# LED_Board_-_SCH_v1_0_0_20210410.net
KiCad netlist of a schematic drawn in Altium Designer
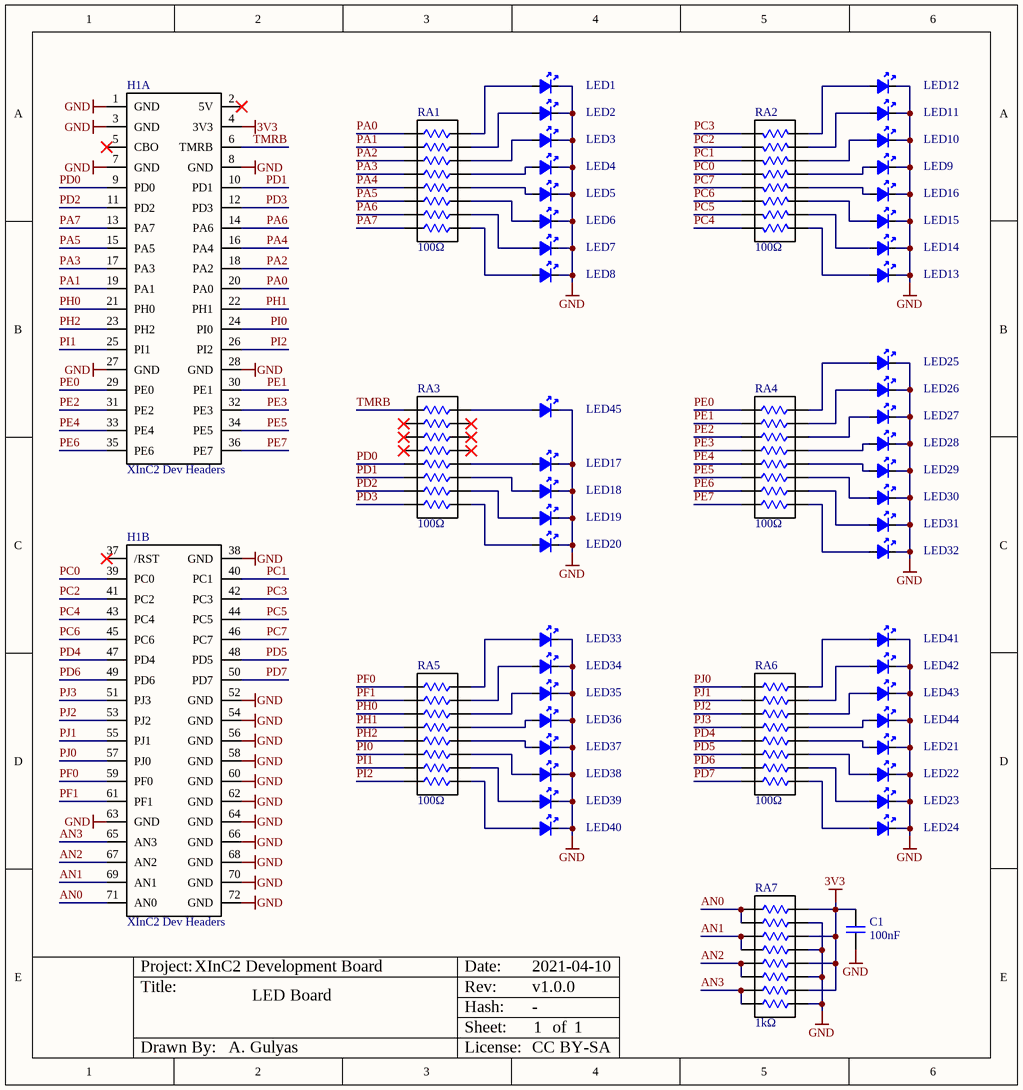
[diagram p0: LED Board - SCH v1.0.0 20210410.SchDoc]

(export (version "E")
  (design (tool "Eeschema 10.0.6"))
  (components
    (comp (ref "C1")
      (value "100nF")
      (footprint "0603 - C")
      (description "CAP CER 0.1UF 16V X7R 0603")
      (fields (field (name "MFG") "Yageo") (field (name "TOLERANCE") "±10%"))
      (libsource (lib "Public Library") (part "C - 0603 - 100nF - 16V"))
    )
    (comp (ref "H1")
      (value "XInC2 Dev Headers")
      (footprint "XInC2 Dev Shield")
      (description "Two 2x16 female headers than mate with a XInC2 Dev Board")
      (libsource (lib "Public Library") (part "XInC2 Dev 2 Shield"))
    )
    (comp (ref "LED1")
      (value "Red")
      (footprint "LED - RED - TH")
      (description "LED RED DIFFUSED 5MM ROUND T/H")
      (fields (field (name "MFG") "Würth Elektronik"))
      (libsource (lib "Public Library") (part "LED - TH - Red"))
    )
    (comp (ref "LED2")
      (value "Red")
      (footprint "LED - RED - TH")
      (description "LED RED DIFFUSED 5MM ROUND T/H")
      (fields (field (name "MFG") "Würth Elektronik"))
      (libsource (lib "Public Library") (part "LED - TH - Red"))
    )
    (comp (ref "LED3")
      (value "Red")
      (footprint "LED - RED - TH")
      (description "LED RED DIFFUSED 5MM ROUND T/H")
      (fields (field (name "MFG") "Würth Elektronik"))
      (libsource (lib "Public Library") (part "LED - TH - Red"))
    )
    (comp (ref "LED4")
      (value "Red")
      (footprint "LED - RED - TH")
      (description "LED RED DIFFUSED 5MM ROUND T/H")
      (fields (field (name "MFG") "Würth Elektronik"))
      (libsource (lib "Public Library") (part "LED - TH - Red"))
    )
    (comp (ref "LED5")
      (value "Red")
      (footprint "LED - RED - TH")
      (description "LED RED DIFFUSED 5MM ROUND T/H")
      (fields (field (name "MFG") "Würth Elektronik"))
      (libsource (lib "Public Library") (part "LED - TH - Red"))
    )
    (comp (ref "LED6")
      (value "Red")
      (footprint "LED - RED - TH")
      (description "LED RED DIFFUSED 5MM ROUND T/H")
      (fields (field (name "MFG") "Würth Elektronik"))
      (libsource (lib "Public Library") (part "LED - TH - Red"))
    )
    (comp (ref "LED7")
      (value "Red")
      (footprint "LED - RED - TH")
      (description "LED RED DIFFUSED 5MM ROUND T/H")
      (fields (field (name "MFG") "Würth Elektronik"))
      (libsource (lib "Public Library") (part "LED - TH - Red"))
    )
    (comp (ref "LED8")
      (value "Red")
      (footprint "LED - RED - TH")
      (description "LED RED DIFFUSED 5MM ROUND T/H")
      (fields (field (name "MFG") "Würth Elektronik"))
      (libsource (lib "Public Library") (part "LED - TH - Red"))
    )
    (comp (ref "LED9")
      (value "Red")
      (footprint "LED - RED - TH")
      (description "LED RED DIFFUSED 5MM ROUND T/H")
      (fields (field (name "MFG") "Würth Elektronik"))
      (libsource (lib "Public Library") (part "LED - TH - Red"))
    )
    (comp (ref "LED10")
      (value "Red")
      (footprint "LED - RED - TH")
      (description "LED RED DIFFUSED 5MM ROUND T/H")
      (fields (field (name "MFG") "Würth Elektronik"))
      (libsource (lib "Public Library") (part "LED - TH - Red"))
    )
    (comp (ref "LED11")
      (value "Red")
      (footprint "LED - RED - TH")
      (description "LED RED DIFFUSED 5MM ROUND T/H")
      (fields (field (name "MFG") "Würth Elektronik"))
      (libsource (lib "Public Library") (part "LED - TH - Red"))
    )
    (comp (ref "LED12")
      (value "Red")
      (footprint "LED - RED - TH")
      (description "LED RED DIFFUSED 5MM ROUND T/H")
      (fields (field (name "MFG") "Würth Elektronik"))
      (libsource (lib "Public Library") (part "LED - TH - Red"))
    )
    (comp (ref "LED13")
      (value "Red")
      (footprint "LED - RED - TH")
      (description "LED RED DIFFUSED 5MM ROUND T/H")
      (fields (field (name "MFG") "Würth Elektronik"))
      (libsource (lib "Public Library") (part "LED - TH - Red"))
    )
    (comp (ref "LED14")
      (value "Red")
      (footprint "LED - RED - TH")
      (description "LED RED DIFFUSED 5MM ROUND T/H")
      (fields (field (name "MFG") "Würth Elektronik"))
      (libsource (lib "Public Library") (part "LED - TH - Red"))
    )
    (comp (ref "LED15")
      (value "Red")
      (footprint "LED - RED - TH")
      (description "LED RED DIFFUSED 5MM ROUND T/H")
      (fields (field (name "MFG") "Würth Elektronik"))
      (libsource (lib "Public Library") (part "LED - TH - Red"))
    )
    (comp (ref "LED16")
      (value "Red")
      (footprint "LED - RED - TH")
      (description "LED RED DIFFUSED 5MM ROUND T/H")
      (fields (field (name "MFG") "Würth Elektronik"))
      (libsource (lib "Public Library") (part "LED - TH - Red"))
    )
    (comp (ref "LED17")
      (value "Red")
      (footprint "LED - RED - TH")
      (description "LED RED DIFFUSED 5MM ROUND T/H")
      (fields (field (name "MFG") "Würth Elektronik"))
      (libsource (lib "Public Library") (part "LED - TH - Red"))
    )
    (comp (ref "LED18")
      (value "Red")
      (footprint "LED - RED - TH")
      (description "LED RED DIFFUSED 5MM ROUND T/H")
      (fields (field (name "MFG") "Würth Elektronik"))
      (libsource (lib "Public Library") (part "LED - TH - Red"))
    )
    (comp (ref "LED19")
      (value "Red")
      (footprint "LED - RED - TH")
      (description "LED RED DIFFUSED 5MM ROUND T/H")
      (fields (field (name "MFG") "Würth Elektronik"))
      (libsource (lib "Public Library") (part "LED - TH - Red"))
    )
    (comp (ref "LED20")
      (value "Red")
      (footprint "LED - RED - TH")
      (description "LED RED DIFFUSED 5MM ROUND T/H")
      (fields (field (name "MFG") "Würth Elektronik"))
      (libsource (lib "Public Library") (part "LED - TH - Red"))
    )
    (comp (ref "LED21")
      (value "Red")
      (footprint "LED - RED - TH")
      (description "LED RED DIFFUSED 5MM ROUND T/H")
      (fields (field (name "MFG") "Würth Elektronik"))
      (libsource (lib "Public Library") (part "LED - TH - Red"))
    )
    (comp (ref "LED22")
      (value "Red")
      (footprint "LED - RED - TH")
      (description "LED RED DIFFUSED 5MM ROUND T/H")
      (fields (field (name "MFG") "Würth Elektronik"))
      (libsource (lib "Public Library") (part "LED - TH - Red"))
    )
    (comp (ref "LED23")
      (value "Red")
      (footprint "LED - RED - TH")
      (description "LED RED DIFFUSED 5MM ROUND T/H")
      (fields (field (name "MFG") "Würth Elektronik"))
      (libsource (lib "Public Library") (part "LED - TH - Red"))
    )
    (comp (ref "LED24")
      (value "Red")
      (footprint "LED - RED - TH")
      (description "LED RED DIFFUSED 5MM ROUND T/H")
      (fields (field (name "MFG") "Würth Elektronik"))
      (libsource (lib "Public Library") (part "LED - TH - Red"))
    )
    (comp (ref "LED25")
      (value "Red")
      (footprint "LED - RED - TH")
      (description "LED RED DIFFUSED 5MM ROUND T/H")
      (fields (field (name "MFG") "Würth Elektronik"))
      (libsource (lib "Public Library") (part "LED - TH - Red"))
    )
    (comp (ref "LED26")
      (value "Red")
      (footprint "LED - RED - TH")
      (description "LED RED DIFFUSED 5MM ROUND T/H")
      (fields (field (name "MFG") "Würth Elektronik"))
      (libsource (lib "Public Library") (part "LED - TH - Red"))
    )
    (comp (ref "LED27")
      (value "Red")
      (footprint "LED - RED - TH")
      (description "LED RED DIFFUSED 5MM ROUND T/H")
      (fields (field (name "MFG") "Würth Elektronik"))
      (libsource (lib "Public Library") (part "LED - TH - Red"))
    )
    (comp (ref "LED28")
      (value "Red")
      (footprint "LED - RED - TH")
      (description "LED RED DIFFUSED 5MM ROUND T/H")
      (fields (field (name "MFG") "Würth Elektronik"))
      (libsource (lib "Public Library") (part "LED - TH - Red"))
    )
    (comp (ref "LED29")
      (value "Red")
      (footprint "LED - RED - TH")
      (description "LED RED DIFFUSED 5MM ROUND T/H")
      (fields (field (name "MFG") "Würth Elektronik"))
      (libsource (lib "Public Library") (part "LED - TH - Red"))
    )
    (comp (ref "LED30")
      (value "Red")
      (footprint "LED - RED - TH")
      (description "LED RED DIFFUSED 5MM ROUND T/H")
      (fields (field (name "MFG") "Würth Elektronik"))
      (libsource (lib "Public Library") (part "LED - TH - Red"))
    )
    (comp (ref "LED31")
      (value "Red")
      (footprint "LED - RED - TH")
      (description "LED RED DIFFUSED 5MM ROUND T/H")
      (fields (field (name "MFG") "Würth Elektronik"))
      (libsource (lib "Public Library") (part "LED - TH - Red"))
    )
    (comp (ref "LED32")
      (value "Red")
      (footprint "LED - RED - TH")
      (description "LED RED DIFFUSED 5MM ROUND T/H")
      (fields (field (name "MFG") "Würth Elektronik"))
      (libsource (lib "Public Library") (part "LED - TH - Red"))
    )
    (comp (ref "LED33")
      (value "Red")
      (footprint "LED - RED - TH")
      (description "LED RED DIFFUSED 5MM ROUND T/H")
      (fields (field (name "MFG") "Würth Elektronik"))
      (libsource (lib "Public Library") (part "LED - TH - Red"))
    )
    (comp (ref "LED34")
      (value "Red")
      (footprint "LED - RED - TH")
      (description "LED RED DIFFUSED 5MM ROUND T/H")
      (fields (field (name "MFG") "Würth Elektronik"))
      (libsource (lib "Public Library") (part "LED - TH - Red"))
    )
    (comp (ref "LED35")
      (value "Red")
      (footprint "LED - RED - TH")
      (description "LED RED DIFFUSED 5MM ROUND T/H")
      (fields (field (name "MFG") "Würth Elektronik"))
      (libsource (lib "Public Library") (part "LED - TH - Red"))
    )
    (comp (ref "LED36")
      (value "Red")
      (footprint "LED - RED - TH")
      (description "LED RED DIFFUSED 5MM ROUND T/H")
      (fields (field (name "MFG") "Würth Elektronik"))
      (libsource (lib "Public Library") (part "LED - TH - Red"))
    )
    (comp (ref "LED37")
      (value "Red")
      (footprint "LED - RED - TH")
      (description "LED RED DIFFUSED 5MM ROUND T/H")
      (fields (field (name "MFG") "Würth Elektronik"))
      (libsource (lib "Public Library") (part "LED - TH - Red"))
    )
    (comp (ref "LED38")
      (value "Red")
      (footprint "LED - RED - TH")
      (description "LED RED DIFFUSED 5MM ROUND T/H")
      (fields (field (name "MFG") "Würth Elektronik"))
      (libsource (lib "Public Library") (part "LED - TH - Red"))
    )
    (comp (ref "LED39")
      (value "Red")
      (footprint "LED - RED - TH")
      (description "LED RED DIFFUSED 5MM ROUND T/H")
      (fields (field (name "MFG") "Würth Elektronik"))
      (libsource (lib "Public Library") (part "LED - TH - Red"))
    )
    (comp (ref "LED40")
      (value "Red")
      (footprint "LED - RED - TH")
      (description "LED RED DIFFUSED 5MM ROUND T/H")
      (fields (field (name "MFG") "Würth Elektronik"))
      (libsource (lib "Public Library") (part "LED - TH - Red"))
    )
    (comp (ref "LED41")
      (value "Red")
      (footprint "LED - RED - TH")
      (description "LED RED DIFFUSED 5MM ROUND T/H")
      (fields (field (name "MFG") "Würth Elektronik"))
      (libsource (lib "Public Library") (part "LED - TH - Red"))
    )
    (comp (ref "LED42")
      (value "Red")
      (footprint "LED - RED - TH")
      (description "LED RED DIFFUSED 5MM ROUND T/H")
      (fields (field (name "MFG") "Würth Elektronik"))
      (libsource (lib "Public Library") (part "LED - TH - Red"))
    )
    (comp (ref "LED43")
      (value "Red")
      (footprint "LED - RED - TH")
      (description "LED RED DIFFUSED 5MM ROUND T/H")
      (fields (field (name "MFG") "Würth Elektronik"))
      (libsource (lib "Public Library") (part "LED - TH - Red"))
    )
    (comp (ref "LED44")
      (value "Red")
      (footprint "LED - RED - TH")
      (description "LED RED DIFFUSED 5MM ROUND T/H")
      (fields (field (name "MFG") "Würth Elektronik"))
      (libsource (lib "Public Library") (part "LED - TH - Red"))
    )
    (comp (ref "LED45")
      (value "Red")
      (footprint "LED - RED - TH")
      (description "LED RED DIFFUSED 5MM ROUND T/H")
      (fields (field (name "MFG") "Würth Elektronik"))
      (libsource (lib "Public Library") (part "LED - TH - Red"))
    )
    (comp (ref "RA1")
      (value "100Ω")
      (footprint "0616 - 8 R array")
      (description "RES ARRAY 8 RES 100 OHM 1606")
      (fields (field (name "TOLERANCE") "±5%"))
      (libsource (lib "") (part "RA - 100Ω - 8_1"))
    )
    (comp (ref "RA2")
      (value "100Ω")
      (footprint "0616 - 8 R array")
      (description "RES ARRAY 8 RES 100 OHM 1606")
      (fields (field (name "TOLERANCE") "±5%"))
      (libsource (lib "Public Library") (part "RA - 100Ω - 8"))
    )
    (comp (ref "RA3")
      (value "100Ω")
      (footprint "0616 - 8 R array")
      (description "RES ARRAY 8 RES 100 OHM 1606")
      (fields (field (name "TOLERANCE") "±5%"))
      (libsource (lib "") (part "RA - 100Ω - 8_1"))
    )
    (comp (ref "RA4")
      (value "100Ω")
      (footprint "0616 - 8 R array")
      (description "RES ARRAY 8 RES 100 OHM 1606")
      (fields (field (name "TOLERANCE") "±5%"))
      (libsource (lib "") (part "RA - 100Ω - 8_1"))
    )
    (comp (ref "RA5")
      (value "100Ω")
      (footprint "0616 - 8 R array")
      (description "RES ARRAY 8 RES 100 OHM 1606")
      (fields (field (name "TOLERANCE") "±5%"))
      (libsource (lib "") (part "RA - 100Ω - 8_1"))
    )
    (comp (ref "RA6")
      (value "100Ω")
      (footprint "0616 - 8 R array")
      (description "RES ARRAY 8 RES 100 OHM 1606")
      (fields (field (name "TOLERANCE") "±5%"))
      (libsource (lib "") (part "RA - 100Ω - 8_2"))
    )
    (comp (ref "RA7")
      (value "1kΩ")
      (footprint "0616 - 8 R array")
      (description "RES ARRAY 8 RES 1K OHM 1606")
      (fields (field (name "TOLERANCE") "±5%"))
      (libsource (lib "Public Library") (part "RA - 1kΩ - 8"))
    )
  )
  (nets
    (net (code "1") (name "/AN0") (class "Default")
      (node (ref "H1") (pin "71") (pinfunction "AN0_71") (pintype "passive"))
      (node (ref "RA7") (pin "10") (pinfunction "10_10") (pintype "passive"))
      (node (ref "RA7") (pin "9") (pinfunction "9_9") (pintype "passive"))
    )
    (net (code "2") (name "/AN1") (class "Default")
      (node (ref "H1") (pin "69") (pinfunction "AN1_69") (pintype "passive"))
      (node (ref "RA7") (pin "11") (pinfunction "11_11") (pintype "passive"))
      (node (ref "RA7") (pin "12") (pinfunction "12_12") (pintype "passive"))
    )
    (net (code "3") (name "/AN2") (class "Default")
      (node (ref "H1") (pin "67") (pinfunction "AN2_67") (pintype "passive"))
      (node (ref "RA7") (pin "13") (pinfunction "13_13") (pintype "passive"))
      (node (ref "RA7") (pin "14") (pinfunction "14_14") (pintype "passive"))
    )
    (net (code "4") (name "/AN3") (class "Default")
      (node (ref "H1") (pin "65") (pinfunction "AN3_65") (pintype "passive"))
      (node (ref "RA7") (pin "15") (pinfunction "15_15") (pintype "passive"))
      (node (ref "RA7") (pin "16") (pinfunction "16_16") (pintype "passive"))
    )
    (net (code "5") (name "/PA0") (class "Default")
      (node (ref "H1") (pin "20") (pinfunction "PA0_20") (pintype "passive"))
      (node (ref "RA1") (pin "1") (pinfunction "1_1") (pintype "passive"))
    )
    (net (code "6") (name "/PA1") (class "Default")
      (node (ref "H1") (pin "19") (pinfunction "PA1_19") (pintype "passive"))
      (node (ref "RA1") (pin "2") (pinfunction "2_2") (pintype "passive"))
    )
    (net (code "7") (name "/PA2") (class "Default")
      (node (ref "H1") (pin "18") (pinfunction "PA2_18") (pintype "passive"))
      (node (ref "RA1") (pin "3") (pinfunction "3_3") (pintype "passive"))
    )
    (net (code "8") (name "/PA3") (class "Default")
      (node (ref "H1") (pin "17") (pinfunction "PA3_17") (pintype "passive"))
      (node (ref "RA1") (pin "4") (pinfunction "4_4") (pintype "passive"))
    )
    (net (code "9") (name "/PA4") (class "Default")
      (node (ref "H1") (pin "16") (pinfunction "PA4_16") (pintype "passive"))
      (node (ref "RA1") (pin "5") (pinfunction "5_5") (pintype "passive"))
    )
    (net (code "10") (name "/PA5") (class "Default")
      (node (ref "H1") (pin "15") (pinfunction "PA5_15") (pintype "passive"))
      (node (ref "RA1") (pin "6") (pinfunction "6_6") (pintype "passive"))
    )
    (net (code "11") (name "/PA6") (class "Default")
      (node (ref "H1") (pin "14") (pinfunction "PA6_14") (pintype "passive"))
      (node (ref "RA1") (pin "7") (pinfunction "7_7") (pintype "passive"))
    )
    (net (code "12") (name "/PA7") (class "Default")
      (node (ref "H1") (pin "13") (pinfunction "PA7_13") (pintype "passive"))
      (node (ref "RA1") (pin "8") (pinfunction "8_8") (pintype "passive"))
    )
    (net (code "13") (name "/PC0") (class "Default")
      (node (ref "H1") (pin "39") (pinfunction "PC0_39") (pintype "passive"))
      (node (ref "RA2") (pin "13") (pinfunction "13_13") (pintype "passive"))
    )
    (net (code "14") (name "/PC1") (class "Default")
      (node (ref "H1") (pin "40") (pinfunction "PC1_40") (pintype "passive"))
      (node (ref "RA2") (pin "14") (pinfunction "14_14") (pintype "passive"))
    )
    (net (code "15") (name "/PC2") (class "Default")
      (node (ref "H1") (pin "41") (pinfunction "PC2_41") (pintype "passive"))
      (node (ref "RA2") (pin "15") (pinfunction "15_15") (pintype "passive"))
    )
    (net (code "16") (name "/PC3") (class "Default")
      (node (ref "H1") (pin "42") (pinfunction "PC3_42") (pintype "passive"))
      (node (ref "RA2") (pin "16") (pinfunction "16_16") (pintype "passive"))
    )
    (net (code "17") (name "/PC4") (class "Default")
      (node (ref "H1") (pin "43") (pinfunction "PC4_43") (pintype "passive"))
      (node (ref "RA2") (pin "9") (pinfunction "9_9") (pintype "passive"))
    )
    (net (code "18") (name "/PC5") (class "Default")
      (node (ref "H1") (pin "44") (pinfunction "PC5_44") (pintype "passive"))
      (node (ref "RA2") (pin "10") (pinfunction "10_10") (pintype "passive"))
    )
    (net (code "19") (name "/PC6") (class "Default")
      (node (ref "H1") (pin "45") (pinfunction "PC6_45") (pintype "passive"))
      (node (ref "RA2") (pin "11") (pinfunction "11_11") (pintype "passive"))
    )
    (net (code "20") (name "/PC7") (class "Default")
      (node (ref "H1") (pin "46") (pinfunction "PC7_46") (pintype "passive"))
      (node (ref "RA2") (pin "12") (pinfunction "12_12") (pintype "passive"))
    )
    (net (code "21") (name "/PD0") (class "Default")
      (node (ref "H1") (pin "9") (pinfunction "PD0_9") (pintype "passive"))
      (node (ref "RA3") (pin "5") (pinfunction "5_5") (pintype "passive"))
    )
    (net (code "22") (name "/PD1") (class "Default")
      (node (ref "H1") (pin "10") (pinfunction "PD1_10") (pintype "passive"))
      (node (ref "RA3") (pin "6") (pinfunction "6_6") (pintype "passive"))
    )
    (net (code "23") (name "/PD2") (class "Default")
      (node (ref "H1") (pin "11") (pinfunction "PD2_11") (pintype "passive"))
      (node (ref "RA3") (pin "7") (pinfunction "7_7") (pintype "passive"))
    )
    (net (code "24") (name "/PD3") (class "Default")
      (node (ref "H1") (pin "12") (pinfunction "PD3_12") (pintype "passive"))
      (node (ref "RA3") (pin "8") (pinfunction "8_8") (pintype "passive"))
    )
    (net (code "25") (name "/PD4") (class "Default")
      (node (ref "H1") (pin "47") (pinfunction "PD4_47") (pintype "passive"))
      (node (ref "RA6") (pin "13") (pinfunction "13_13") (pintype "passive"))
    )
    (net (code "26") (name "/PD5") (class "Default")
      (node (ref "H1") (pin "48") (pinfunction "PD5_48") (pintype "passive"))
      (node (ref "RA6") (pin "14") (pinfunction "14_14") (pintype "passive"))
    )
    (net (code "27") (name "/PD6") (class "Default")
      (node (ref "H1") (pin "49") (pinfunction "PD6_49") (pintype "passive"))
      (node (ref "RA6") (pin "15") (pinfunction "15_15") (pintype "passive"))
    )
    (net (code "28") (name "/PD7") (class "Default")
      (node (ref "H1") (pin "50") (pinfunction "PD7_50") (pintype "passive"))
      (node (ref "RA6") (pin "16") (pinfunction "16_16") (pintype "passive"))
    )
    (net (code "29") (name "/PE0") (class "Default")
      (node (ref "H1") (pin "29") (pinfunction "PE0_29") (pintype "passive"))
      (node (ref "RA4") (pin "1") (pinfunction "1_1") (pintype "passive"))
    )
    (net (code "30") (name "/PE1") (class "Default")
      (node (ref "H1") (pin "30") (pinfunction "PE1_30") (pintype "passive"))
      (node (ref "RA4") (pin "2") (pinfunction "2_2") (pintype "passive"))
    )
    (net (code "31") (name "/PE2") (class "Default")
      (node (ref "H1") (pin "31") (pinfunction "PE2_31") (pintype "passive"))
      (node (ref "RA4") (pin "3") (pinfunction "3_3") (pintype "passive"))
    )
    (net (code "32") (name "/PE3") (class "Default")
      (node (ref "H1") (pin "32") (pinfunction "PE3_32") (pintype "passive"))
      (node (ref "RA4") (pin "4") (pinfunction "4_4") (pintype "passive"))
    )
    (net (code "33") (name "/PE4") (class "Default")
      (node (ref "H1") (pin "33") (pinfunction "PE4_33") (pintype "passive"))
      (node (ref "RA4") (pin "5") (pinfunction "5_5") (pintype "passive"))
    )
    (net (code "34") (name "/PE5") (class "Default")
      (node (ref "H1") (pin "34") (pinfunction "PE5_34") (pintype "passive"))
      (node (ref "RA4") (pin "6") (pinfunction "6_6") (pintype "passive"))
    )
    (net (code "35") (name "/PE6") (class "Default")
      (node (ref "H1") (pin "35") (pinfunction "PE6_35") (pintype "passive"))
      (node (ref "RA4") (pin "7") (pinfunction "7_7") (pintype "passive"))
    )
    (net (code "36") (name "/PE7") (class "Default")
      (node (ref "H1") (pin "36") (pinfunction "PE7_36") (pintype "passive"))
      (node (ref "RA4") (pin "8") (pinfunction "8_8") (pintype "passive"))
    )
    (net (code "37") (name "/PF0") (class "Default")
      (node (ref "H1") (pin "59") (pinfunction "PF0_59") (pintype "passive"))
      (node (ref "RA5") (pin "1") (pinfunction "1_1") (pintype "passive"))
    )
    (net (code "38") (name "/PF1") (class "Default")
      (node (ref "H1") (pin "61") (pinfunction "PF1_61") (pintype "passive"))
      (node (ref "RA5") (pin "2") (pinfunction "2_2") (pintype "passive"))
    )
    (net (code "39") (name "/PH0") (class "Default")
      (node (ref "H1") (pin "21") (pinfunction "PH0_21") (pintype "passive"))
      (node (ref "RA5") (pin "3") (pinfunction "3_3") (pintype "passive"))
    )
    (net (code "40") (name "/PH1") (class "Default")
      (node (ref "H1") (pin "22") (pinfunction "PH1_22") (pintype "passive"))
      (node (ref "RA5") (pin "4") (pinfunction "4_4") (pintype "passive"))
    )
    (net (code "41") (name "/PH2") (class "Default")
      (node (ref "H1") (pin "23") (pinfunction "PH2_23") (pintype "passive"))
      (node (ref "RA5") (pin "5") (pinfunction "5_5") (pintype "passive"))
    )
    (net (code "42") (name "/PI0") (class "Default")
      (node (ref "H1") (pin "24") (pinfunction "PI0_24") (pintype "passive"))
      (node (ref "RA5") (pin "6") (pinfunction "6_6") (pintype "passive"))
    )
    (net (code "43") (name "/PI1") (class "Default")
      (node (ref "H1") (pin "25") (pinfunction "PI1_25") (pintype "passive"))
      (node (ref "RA5") (pin "7") (pinfunction "7_7") (pintype "passive"))
    )
    (net (code "44") (name "/PI2") (class "Default")
      (node (ref "H1") (pin "26") (pinfunction "PI2_26") (pintype "passive"))
      (node (ref "RA5") (pin "8") (pinfunction "8_8") (pintype "passive"))
    )
    (net (code "45") (name "/PJ0") (class "Default")
      (node (ref "H1") (pin "57") (pinfunction "PJ0_57") (pintype "passive"))
      (node (ref "RA6") (pin "9") (pinfunction "9_9") (pintype "passive"))
    )
    (net (code "46") (name "/PJ1") (class "Default")
      (node (ref "H1") (pin "55") (pinfunction "PJ1_55") (pintype "passive"))
      (node (ref "RA6") (pin "10") (pinfunction "10_10") (pintype "passive"))
    )
    (net (code "47") (name "/PJ2") (class "Default")
      (node (ref "H1") (pin "53") (pinfunction "PJ2_53") (pintype "passive"))
      (node (ref "RA6") (pin "11") (pinfunction "11_11") (pintype "passive"))
    )
    (net (code "48") (name "/PJ3") (class "Default")
      (node (ref "H1") (pin "51") (pinfunction "PJ3_51") (pintype "passive"))
      (node (ref "RA6") (pin "12") (pinfunction "12_12") (pintype "passive"))
    )
    (net (code "49") (name "/TMRB") (class "Default")
      (node (ref "H1") (pin "6") (pinfunction "TMRB_6") (pintype "passive"))
      (node (ref "RA3") (pin "1") (pinfunction "1_1") (pintype "passive"))
    )
    (net (code "50") (name "3V3") (class "Default")
      (node (ref "C1") (pin "1") (pinfunction "1_1") (pintype "passive"))
      (node (ref "H1") (pin "4") (pinfunction "3V3_4") (pintype "passive"))
      (node (ref "RA7") (pin "2") (pinfunction "2_2") (pintype "passive"))
      (node (ref "RA7") (pin "4") (pinfunction "4_4") (pintype "passive"))
      (node (ref "RA7") (pin "6") (pinfunction "6_6") (pintype "passive"))
      (node (ref "RA7") (pin "8") (pinfunction "8_8") (pintype "passive"))
    )
    (net (code "51") (name "GND") (class "Default")
      (node (ref "C1") (pin "2") (pinfunction "2_2") (pintype "passive"))
      (node (ref "H1") (pin "1") (pinfunction "GND_1") (pintype "passive"))
      (node (ref "H1") (pin "27") (pinfunction "GND_27") (pintype "passive"))
      (node (ref "H1") (pin "28") (pinfunction "GND_28") (pintype "passive"))
      (node (ref "H1") (pin "3") (pinfunction "GND_3") (pintype "passive"))
      (node (ref "H1") (pin "38") (pinfunction "GND_38") (pintype "passive"))
      (node (ref "H1") (pin "52") (pinfunction "GND_52") (pintype "passive"))
      (node (ref "H1") (pin "54") (pinfunction "GND_54") (pintype "passive"))
      (node (ref "H1") (pin "56") (pinfunction "GND_56") (pintype "passive"))
      (node (ref "H1") (pin "58") (pinfunction "GND_58") (pintype "passive"))
      (node (ref "H1") (pin "60") (pinfunction "GND_60") (pintype "passive"))
      (node (ref "H1") (pin "62") (pinfunction "GND_62") (pintype "passive"))
      (node (ref "H1") (pin "63") (pinfunction "GND_63") (pintype "passive"))
      (node (ref "H1") (pin "64") (pinfunction "GND_64") (pintype "passive"))
      (node (ref "H1") (pin "66") (pinfunction "GND_66") (pintype "passive"))
      (node (ref "H1") (pin "68") (pinfunction "GND_68") (pintype "passive"))
      (node (ref "H1") (pin "7") (pinfunction "GND_7") (pintype "passive"))
      (node (ref "H1") (pin "70") (pinfunction "GND_70") (pintype "passive"))
      (node (ref "H1") (pin "72") (pinfunction "GND_72") (pintype "passive"))
      (node (ref "H1") (pin "8") (pinfunction "GND_8") (pintype "passive"))
      (node (ref "LED1") (pin "2") (pinfunction "2_2") (pintype "passive"))
      (node (ref "LED10") (pin "2") (pinfunction "2_2") (pintype "passive"))
      (node (ref "LED11") (pin "2") (pinfunction "2_2") (pintype "passive"))
      (node (ref "LED12") (pin "2") (pinfunction "2_2") (pintype "passive"))
      (node (ref "LED13") (pin "2") (pinfunction "2_2") (pintype "passive"))
      (node (ref "LED14") (pin "2") (pinfunction "2_2") (pintype "passive"))
      (node (ref "LED15") (pin "2") (pinfunction "2_2") (pintype "passive"))
      (node (ref "LED16") (pin "2") (pinfunction "2_2") (pintype "passive"))
      (node (ref "LED17") (pin "2") (pinfunction "2_2") (pintype "passive"))
      (node (ref "LED18") (pin "2") (pinfunction "2_2") (pintype "passive"))
      (node (ref "LED19") (pin "2") (pinfunction "2_2") (pintype "passive"))
      (node (ref "LED2") (pin "2") (pinfunction "2_2") (pintype "passive"))
      (node (ref "LED20") (pin "2") (pinfunction "2_2") (pintype "passive"))
      (node (ref "LED21") (pin "2") (pinfunction "2_2") (pintype "passive"))
      (node (ref "LED22") (pin "2") (pinfunction "2_2") (pintype "passive"))
      (node (ref "LED23") (pin "2") (pinfunction "2_2") (pintype "passive"))
      (node (ref "LED24") (pin "2") (pinfunction "2_2") (pintype "passive"))
      (node (ref "LED25") (pin "2") (pinfunction "2_2") (pintype "passive"))
      (node (ref "LED26") (pin "2") (pinfunction "2_2") (pintype "passive"))
      (node (ref "LED27") (pin "2") (pinfunction "2_2") (pintype "passive"))
      (node (ref "LED28") (pin "2") (pinfunction "2_2") (pintype "passive"))
      (node (ref "LED29") (pin "2") (pinfunction "2_2") (pintype "passive"))
      (node (ref "LED3") (pin "2") (pinfunction "2_2") (pintype "passive"))
      (node (ref "LED30") (pin "2") (pinfunction "2_2") (pintype "passive"))
      (node (ref "LED31") (pin "2") (pinfunction "2_2") (pintype "passive"))
      (node (ref "LED32") (pin "2") (pinfunction "2_2") (pintype "passive"))
      (node (ref "LED33") (pin "2") (pinfunction "2_2") (pintype "passive"))
      (node (ref "LED34") (pin "2") (pinfunction "2_2") (pintype "passive"))
      (node (ref "LED35") (pin "2") (pinfunction "2_2") (pintype "passive"))
      (node (ref "LED36") (pin "2") (pinfunction "2_2") (pintype "passive"))
      (node (ref "LED37") (pin "2") (pinfunction "2_2") (pintype "passive"))
      (node (ref "LED38") (pin "2") (pinfunction "2_2") (pintype "passive"))
      (node (ref "LED39") (pin "2") (pinfunction "2_2") (pintype "passive"))
      (node (ref "LED4") (pin "2") (pinfunction "2_2") (pintype "passive"))
      (node (ref "LED40") (pin "2") (pinfunction "2_2") (pintype "passive"))
      (node (ref "LED41") (pin "2") (pinfunction "2_2") (pintype "passive"))
      (node (ref "LED42") (pin "2") (pinfunction "2_2") (pintype "passive"))
      (node (ref "LED43") (pin "2") (pinfunction "2_2") (pintype "passive"))
      (node (ref "LED44") (pin "2") (pinfunction "2_2") (pintype "passive"))
      (node (ref "LED45") (pin "2") (pinfunction "2_2") (pintype "passive"))
      (node (ref "LED5") (pin "2") (pinfunction "2_2") (pintype "passive"))
      (node (ref "LED6") (pin "2") (pinfunction "2_2") (pintype "passive"))
      (node (ref "LED7") (pin "2") (pinfunction "2_2") (pintype "passive"))
      (node (ref "LED8") (pin "2") (pinfunction "2_2") (pintype "passive"))
      (node (ref "LED9") (pin "2") (pinfunction "2_2") (pintype "passive"))
      (node (ref "RA7") (pin "1") (pinfunction "1_1") (pintype "passive"))
      (node (ref "RA7") (pin "3") (pinfunction "3_3") (pintype "passive"))
      (node (ref "RA7") (pin "5") (pinfunction "5_5") (pintype "passive"))
      (node (ref "RA7") (pin "7") (pinfunction "7_7") (pintype "passive"))
    )
    (net (code "52") (name "Net-(LED1-Pad1)") (class "Default")
      (node (ref "LED1") (pin "1") (pinfunction "1_1") (pintype "passive"))
      (node (ref "RA1") (pin "16") (pinfunction "16_16") (pintype "passive"))
    )
    (net (code "53") (name "Net-(LED2-Pad1)") (class "Default")
      (node (ref "LED2") (pin "1") (pinfunction "1_1") (pintype "passive"))
      (node (ref "RA1") (pin "15") (pinfunction "15_15") (pintype "passive"))
    )
    (net (code "54") (name "Net-(LED3-Pad1)") (class "Default")
      (node (ref "LED3") (pin "1") (pinfunction "1_1") (pintype "passive"))
      (node (ref "RA1") (pin "14") (pinfunction "14_14") (pintype "passive"))
    )
    (net (code "55") (name "Net-(LED4-Pad1)") (class "Default")
      (node (ref "LED4") (pin "1") (pinfunction "1_1") (pintype "passive"))
      (node (ref "RA1") (pin "13") (pinfunction "13_13") (pintype "passive"))
    )
    (net (code "56") (name "Net-(LED5-Pad1)") (class "Default")
      (node (ref "LED5") (pin "1") (pinfunction "1_1") (pintype "passive"))
      (node (ref "RA1") (pin "12") (pinfunction "12_12") (pintype "passive"))
    )
    (net (code "57") (name "Net-(LED6-Pad1)") (class "Default")
      (node (ref "LED6") (pin "1") (pinfunction "1_1") (pintype "passive"))
      (node (ref "RA1") (pin "11") (pinfunction "11_11") (pintype "passive"))
    )
    (net (code "58") (name "Net-(LED7-Pad1)") (class "Default")
      (node (ref "LED7") (pin "1") (pinfunction "1_1") (pintype "passive"))
      (node (ref "RA1") (pin "10") (pinfunction "10_10") (pintype "passive"))
    )
    (net (code "59") (name "Net-(LED8-Pad1)") (class "Default")
      (node (ref "LED8") (pin "1") (pinfunction "1_1") (pintype "passive"))
      (node (ref "RA1") (pin "9") (pinfunction "9_9") (pintype "passive"))
    )
    (net (code "60") (name "Net-(LED9-Pad1)") (class "Default")
      (node (ref "LED9") (pin "1") (pinfunction "1_1") (pintype "passive"))
      (node (ref "RA2") (pin "4") (pinfunction "4_4") (pintype "passive"))
    )
    (net (code "61") (name "Net-(LED10-Pad1)") (class "Default")
      (node (ref "LED10") (pin "1") (pinfunction "1_1") (pintype "passive"))
      (node (ref "RA2") (pin "3") (pinfunction "3_3") (pintype "passive"))
    )
    (net (code "62") (name "Net-(LED11-Pad1)") (class "Default")
      (node (ref "LED11") (pin "1") (pinfunction "1_1") (pintype "passive"))
      (node (ref "RA2") (pin "2") (pinfunction "2_2") (pintype "passive"))
    )
    (net (code "63") (name "Net-(LED12-Pad1)") (class "Default")
      (node (ref "LED12") (pin "1") (pinfunction "1_1") (pintype "passive"))
      (node (ref "RA2") (pin "1") (pinfunction "1_1") (pintype "passive"))
    )
    (net (code "64") (name "Net-(LED13-Pad1)") (class "Default")
      (node (ref "LED13") (pin "1") (pinfunction "1_1") (pintype "passive"))
      (node (ref "RA2") (pin "8") (pinfunction "8_8") (pintype "passive"))
    )
    (net (code "65") (name "Net-(LED14-Pad1)") (class "Default")
      (node (ref "LED14") (pin "1") (pinfunction "1_1") (pintype "passive"))
      (node (ref "RA2") (pin "7") (pinfunction "7_7") (pintype "passive"))
    )
    (net (code "66") (name "Net-(LED15-Pad1)") (class "Default")
      (node (ref "LED15") (pin "1") (pinfunction "1_1") (pintype "passive"))
      (node (ref "RA2") (pin "6") (pinfunction "6_6") (pintype "passive"))
    )
    (net (code "67") (name "Net-(LED16-Pad1)") (class "Default")
      (node (ref "LED16") (pin "1") (pinfunction "1_1") (pintype "passive"))
      (node (ref "RA2") (pin "5") (pinfunction "5_5") (pintype "passive"))
    )
    (net (code "68") (name "Net-(LED17-Pad1)") (class "Default")
      (node (ref "LED17") (pin "1") (pinfunction "1_1") (pintype "passive"))
      (node (ref "RA3") (pin "12") (pinfunction "12_12") (pintype "passive"))
    )
    (net (code "69") (name "Net-(LED18-Pad1)") (class "Default")
      (node (ref "LED18") (pin "1") (pinfunction "1_1") (pintype "passive"))
      (node (ref "RA3") (pin "11") (pinfunction "11_11") (pintype "passive"))
    )
    (net (code "70") (name "Net-(LED19-Pad1)") (class "Default")
      (node (ref "LED19") (pin "1") (pinfunction "1_1") (pintype "passive"))
      (node (ref "RA3") (pin "10") (pinfunction "10_10") (pintype "passive"))
    )
    (net (code "71") (name "Net-(LED20-Pad1)") (class "Default")
      (node (ref "LED20") (pin "1") (pinfunction "1_1") (pintype "passive"))
      (node (ref "RA3") (pin "9") (pinfunction "9_9") (pintype "passive"))
    )
    (net (code "72") (name "Net-(LED21-Pad1)") (class "Default")
      (node (ref "LED21") (pin "1") (pinfunction "1_1") (pintype "passive"))
      (node (ref "RA6") (pin "4") (pinfunction "4_4") (pintype "passive"))
    )
    (net (code "73") (name "Net-(LED22-Pad1)") (class "Default")
      (node (ref "LED22") (pin "1") (pinfunction "1_1") (pintype "passive"))
      (node (ref "RA6") (pin "3") (pinfunction "3_3") (pintype "passive"))
    )
    (net (code "74") (name "Net-(LED23-Pad1)") (class "Default")
      (node (ref "LED23") (pin "1") (pinfunction "1_1") (pintype "passive"))
      (node (ref "RA6") (pin "2") (pinfunction "2_2") (pintype "passive"))
    )
    (net (code "75") (name "Net-(LED24-Pad1)") (class "Default")
      (node (ref "LED24") (pin "1") (pinfunction "1_1") (pintype "passive"))
      (node (ref "RA6") (pin "1") (pinfunction "1_1") (pintype "passive"))
    )
    (net (code "76") (name "Net-(LED25-Pad1)") (class "Default")
      (node (ref "LED25") (pin "1") (pinfunction "1_1") (pintype "passive"))
      (node (ref "RA4") (pin "16") (pinfunction "16_16") (pintype "passive"))
    )
    (net (code "77") (name "Net-(LED26-Pad1)") (class "Default")
      (node (ref "LED26") (pin "1") (pinfunction "1_1") (pintype "passive"))
      (node (ref "RA4") (pin "15") (pinfunction "15_15") (pintype "passive"))
    )
    (net (code "78") (name "Net-(LED27-Pad1)") (class "Default")
      (node (ref "LED27") (pin "1") (pinfunction "1_1") (pintype "passive"))
      (node (ref "RA4") (pin "14") (pinfunction "14_14") (pintype "passive"))
    )
    (net (code "79") (name "Net-(LED28-Pad1)") (class "Default")
      (node (ref "LED28") (pin "1") (pinfunction "1_1") (pintype "passive"))
      (node (ref "RA4") (pin "13") (pinfunction "13_13") (pintype "passive"))
    )
    (net (code "80") (name "Net-(LED29-Pad1)") (class "Default")
      (node (ref "LED29") (pin "1") (pinfunction "1_1") (pintype "passive"))
      (node (ref "RA4") (pin "12") (pinfunction "12_12") (pintype "passive"))
    )
    (net (code "81") (name "Net-(LED30-Pad1)") (class "Default")
      (node (ref "LED30") (pin "1") (pinfunction "1_1") (pintype "passive"))
      (node (ref "RA4") (pin "11") (pinfunction "11_11") (pintype "passive"))
    )
    (net (code "82") (name "Net-(LED31-Pad1)") (class "Default")
      (node (ref "LED31") (pin "1") (pinfunction "1_1") (pintype "passive"))
      (node (ref "RA4") (pin "10") (pinfunction "10_10") (pintype "passive"))
    )
    (net (code "83") (name "Net-(LED32-Pad1)") (class "Default")
      (node (ref "LED32") (pin "1") (pinfunction "1_1") (pintype "passive"))
      (node (ref "RA4") (pin "9") (pinfunction "9_9") (pintype "passive"))
    )
    (net (code "84") (name "Net-(LED33-Pad1)") (class "Default")
      (node (ref "LED33") (pin "1") (pinfunction "1_1") (pintype "passive"))
      (node (ref "RA5") (pin "16") (pinfunction "16_16") (pintype "passive"))
    )
    (net (code "85") (name "Net-(LED34-Pad1)") (class "Default")
      (node (ref "LED34") (pin "1") (pinfunction "1_1") (pintype "passive"))
      (node (ref "RA5") (pin "15") (pinfunction "15_15") (pintype "passive"))
    )
    (net (code "86") (name "Net-(LED35-Pad1)") (class "Default")
      (node (ref "LED35") (pin "1") (pinfunction "1_1") (pintype "passive"))
      (node (ref "RA5") (pin "14") (pinfunction "14_14") (pintype "passive"))
    )
    (net (code "87") (name "Net-(LED36-Pad1)") (class "Default")
      (node (ref "LED36") (pin "1") (pinfunction "1_1") (pintype "passive"))
      (node (ref "RA5") (pin "13") (pinfunction "13_13") (pintype "passive"))
    )
    (net (code "88") (name "Net-(LED37-Pad1)") (class "Default")
      (node (ref "LED37") (pin "1") (pinfunction "1_1") (pintype "passive"))
      (node (ref "RA5") (pin "12") (pinfunction "12_12") (pintype "passive"))
    )
    (net (code "89") (name "Net-(LED38-Pad1)") (class "Default")
      (node (ref "LED38") (pin "1") (pinfunction "1_1") (pintype "passive"))
      (node (ref "RA5") (pin "11") (pinfunction "11_11") (pintype "passive"))
    )
    (net (code "90") (name "Net-(LED39-Pad1)") (class "Default")
      (node (ref "LED39") (pin "1") (pinfunction "1_1") (pintype "passive"))
      (node (ref "RA5") (pin "10") (pinfunction "10_10") (pintype "passive"))
    )
    (net (code "91") (name "Net-(LED40-Pad1)") (class "Default")
      (node (ref "LED40") (pin "1") (pinfunction "1_1") (pintype "passive"))
      (node (ref "RA5") (pin "9") (pinfunction "9_9") (pintype "passive"))
    )
    (net (code "92") (name "Net-(LED41-Pad1)") (class "Default")
      (node (ref "LED41") (pin "1") (pinfunction "1_1") (pintype "passive"))
      (node (ref "RA6") (pin "8") (pinfunction "8_8") (pintype "passive"))
    )
    (net (code "93") (name "Net-(LED42-Pad1)") (class "Default")
      (node (ref "LED42") (pin "1") (pinfunction "1_1") (pintype "passive"))
      (node (ref "RA6") (pin "7") (pinfunction "7_7") (pintype "passive"))
    )
    (net (code "94") (name "Net-(LED43-Pad1)") (class "Default")
      (node (ref "LED43") (pin "1") (pinfunction "1_1") (pintype "passive"))
      (node (ref "RA6") (pin "6") (pinfunction "6_6") (pintype "passive"))
    )
    (net (code "95") (name "Net-(LED44-Pad1)") (class "Default")
      (node (ref "LED44") (pin "1") (pinfunction "1_1") (pintype "passive"))
      (node (ref "RA6") (pin "5") (pinfunction "5_5") (pintype "passive"))
    )
    (net (code "96") (name "Net-(LED45-Pad1)") (class "Default")
      (node (ref "LED45") (pin "1") (pinfunction "1_1") (pintype "passive"))
      (node (ref "RA3") (pin "16") (pinfunction "16_16") (pintype "passive"))
    )
    (net (code "97") (name "unconnected-(H1A-5V-Pad2)") (class "Default")
      (node (ref "H1") (pin "2") (pinfunction "5V_2") (pintype "passive+no_connect"))
    )
    (net (code "98") (name "unconnected-(H1A-CBO-Pad5)") (class "Default")
      (node (ref "H1") (pin "5") (pinfunction "CBO_5") (pintype "passive+no_connect"))
    )
    (net (code "99") (name "unconnected-(H1B-{slash}RST-Pad37)") (class "Default")
      (node (ref "H1") (pin "37") (pinfunction "/RST_37") (pintype "passive+no_connect"))
    )
    (net (code "100") (name "unconnected-(RA3-Pad2)") (class "Default")
      (node (ref "RA3") (pin "2") (pinfunction "2_2") (pintype "passive+no_connect"))
    )
    (net (code "101") (name "unconnected-(RA3-Pad3)") (class "Default")
      (node (ref "RA3") (pin "3") (pinfunction "3_3") (pintype "passive+no_connect"))
    )
    (net (code "102") (name "unconnected-(RA3-Pad4)") (class "Default")
      (node (ref "RA3") (pin "4") (pinfunction "4_4") (pintype "passive+no_connect"))
    )
    (net (code "103") (name "unconnected-(RA3-Pad13)") (class "Default")
      (node (ref "RA3") (pin "13") (pinfunction "13_13") (pintype "passive+no_connect"))
    )
    (net (code "104") (name "unconnected-(RA3-Pad14)") (class "Default")
      (node (ref "RA3") (pin "14") (pinfunction "14_14") (pintype "passive+no_connect"))
    )
    (net (code "105") (name "unconnected-(RA3-Pad15)") (class "Default")
      (node (ref "RA3") (pin "15") (pinfunction "15_15") (pintype "passive+no_connect"))
    )
  )
)
